# Placa_Shield_Arduino_Projeto.net
KiCad netlist of a schematic drawn in EAGLE
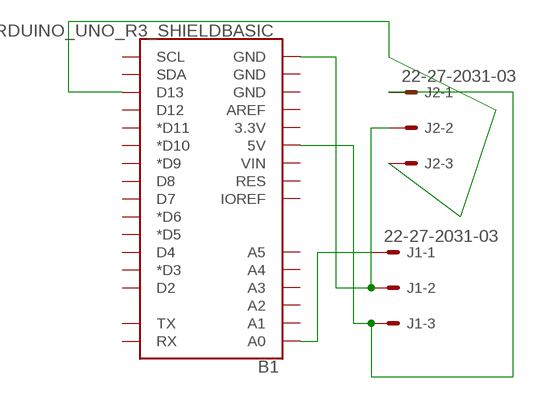
[diagram p0: schematic, sheet 1]

(export (version "E")
  (design (tool "Eeschema 10.0.6"))
  (components
    (comp (ref "B1")
      (value "ARDUINO_UNO_R3_SHIELDBASIC")
      (footprint "eagle-import:UNO_R3_SHIELD")
      (libsource (lib "eagle-import") (part "ARDUINO_UNO_R3_SHIELDBASIC"))
    )
    (comp (ref "J1")
      (value "22-27-2031-03")
      (footprint "eagle-import:6410-03")
      (fields (field (name "MF") "MOLEX"))
      (libsource (lib "eagle-import") (part "22-?-0327-2031"))
    )
    (comp (ref "J2")
      (value "22-27-2031-03")
      (footprint "eagle-import:6410-03")
      (fields (field (name "MF") "MOLEX"))
      (libsource (lib "eagle-import") (part "22-?-0327-2031"))
    )
  )
  (nets
    (net (code "1") (name "Net-(J1A-S)") (class "Default")
      (node (ref "B1") (pin "A0") (pinfunction "A0_A0") (pintype "bidirectional"))
      (node (ref "J1") (pin "1") (pinfunction "S_1") (pintype "passive"))
    )
    (net (code "2") (name "Net-(J1B-S)") (class "Default")
      (node (ref "B1") (pin "GND@0") (pinfunction "GND_GND@0") (pintype "bidirectional"))
      (node (ref "J1") (pin "2") (pinfunction "S_2") (pintype "passive"))
      (node (ref "J2") (pin "2") (pinfunction "S_2") (pintype "passive"))
    )
    (net (code "3") (name "Net-(J1C-S)") (class "Default")
      (node (ref "B1") (pin "5V") (pinfunction "5V_5V") (pintype "bidirectional"))
      (node (ref "J1") (pin "3") (pinfunction "S_3") (pintype "passive"))
      (node (ref "J2") (pin "1") (pinfunction "S_1") (pintype "passive"))
    )
    (net (code "4") (name "Net-(J2C-S)") (class "Default")
      (node (ref "B1") (pin "D13") (pinfunction "D13_D13") (pintype "bidirectional"))
      (node (ref "J2") (pin "3") (pinfunction "S_3") (pintype "passive"))
    )
    (net (code "5") (name "unconnected-(B1-*D3-PadD3)") (class "Default")
      (node (ref "B1") (pin "D3") (pinfunction "*D3_D3") (pintype "bidirectional"))
    )
    (net (code "6") (name "unconnected-(B1-*D5-PadD5)") (class "Default")
      (node (ref "B1") (pin "D5") (pinfunction "*D5_D5") (pintype "bidirectional"))
    )
    (net (code "7") (name "unconnected-(B1-*D6-PadD6)") (class "Default")
      (node (ref "B1") (pin "D6") (pinfunction "*D6_D6") (pintype "bidirectional"))
    )
    (net (code "8") (name "unconnected-(B1-*D9-PadD9)") (class "Default")
      (node (ref "B1") (pin "D9") (pinfunction "*D9_D9") (pintype "bidirectional"))
    )
    (net (code "9") (name "unconnected-(B1-*D10-PadD10)") (class "Default")
      (node (ref "B1") (pin "D10") (pinfunction "*D10_D10") (pintype "bidirectional"))
    )
    (net (code "10") (name "unconnected-(B1-*D11-PadD11)") (class "Default")
      (node (ref "B1") (pin "D11") (pinfunction "*D11_D11") (pintype "bidirectional"))
    )
    (net (code "11") (name "unconnected-(B1-GND-PadGND@1)") (class "Default")
      (node (ref "B1") (pin "GND@1") (pinfunction "GND_GND@1") (pintype "bidirectional"))
    )
    (net (code "12") (name "unconnected-(B1-GND-PadGND@2)") (class "Default")
      (node (ref "B1") (pin "GND@2") (pinfunction "GND_GND@2") (pintype "bidirectional"))
    )
    (net (code "13") (name "unconnected-(B1-Pad3.3V)") (class "Default")
      (node (ref "B1") (pin "3.3V") (pinfunction "3.3V_3.3V") (pintype "bidirectional"))
    )
    (net (code "14") (name "unconnected-(B1-PadA1)") (class "Default")
      (node (ref "B1") (pin "A1") (pinfunction "A1_A1") (pintype "bidirectional"))
    )
    (net (code "15") (name "unconnected-(B1-PadA2)") (class "Default")
      (node (ref "B1") (pin "A2") (pinfunction "A2_A2") (pintype "bidirectional"))
    )
    (net (code "16") (name "unconnected-(B1-PadA3)") (class "Default")
      (node (ref "B1") (pin "A3") (pinfunction "A3_A3") (pintype "bidirectional"))
    )
    (net (code "17") (name "unconnected-(B1-PadA4)") (class "Default")
      (node (ref "B1") (pin "A4") (pinfunction "A4_A4") (pintype "bidirectional"))
    )
    (net (code "18") (name "unconnected-(B1-PadA5)") (class "Default")
      (node (ref "B1") (pin "A5") (pinfunction "A5_A5") (pintype "bidirectional"))
    )
    (net (code "19") (name "unconnected-(B1-PadAREF)") (class "Default")
      (node (ref "B1") (pin "AREF") (pinfunction "AREF_AREF") (pintype "bidirectional"))
    )
    (net (code "20") (name "unconnected-(B1-PadD2)") (class "Default")
      (node (ref "B1") (pin "D2") (pinfunction "D2_D2") (pintype "bidirectional"))
    )
    (net (code "21") (name "unconnected-(B1-PadD4)") (class "Default")
      (node (ref "B1") (pin "D4") (pinfunction "D4_D4") (pintype "bidirectional"))
    )
    (net (code "22") (name "unconnected-(B1-PadD7)") (class "Default")
      (node (ref "B1") (pin "D7") (pinfunction "D7_D7") (pintype "bidirectional"))
    )
    (net (code "23") (name "unconnected-(B1-PadD8)") (class "Default")
      (node (ref "B1") (pin "D8") (pinfunction "D8_D8") (pintype "bidirectional"))
    )
    (net (code "24") (name "unconnected-(B1-PadD12)") (class "Default")
      (node (ref "B1") (pin "D12") (pinfunction "D12_D12") (pintype "bidirectional"))
    )
    (net (code "25") (name "unconnected-(B1-PadIOREF)") (class "Default")
      (node (ref "B1") (pin "IOREF") (pinfunction "IOREF_IOREF") (pintype "bidirectional"))
    )
    (net (code "26") (name "unconnected-(B1-PadRES)") (class "Default")
      (node (ref "B1") (pin "RES") (pinfunction "RES_RES") (pintype "bidirectional"))
    )
    (net (code "27") (name "unconnected-(B1-PadRX)") (class "Default")
      (node (ref "B1") (pin "RX") (pinfunction "RX_RX") (pintype "bidirectional"))
    )
    (net (code "28") (name "unconnected-(B1-PadSCL)") (class "Default")
      (node (ref "B1") (pin "SCL") (pinfunction "SCL_SCL") (pintype "bidirectional"))
    )
    (net (code "29") (name "unconnected-(B1-PadSDA)") (class "Default")
      (node (ref "B1") (pin "SDA") (pinfunction "SDA_SDA") (pintype "bidirectional"))
    )
    (net (code "30") (name "unconnected-(B1-PadTX)") (class "Default")
      (node (ref "B1") (pin "TX") (pinfunction "TX_TX") (pintype "bidirectional"))
    )
    (net (code "31") (name "unconnected-(B1-PadVIN)") (class "Default")
      (node (ref "B1") (pin "VIN") (pinfunction "VIN_VIN") (pintype "bidirectional"))
    )
  )
)
